# LCD.net
KiCad netlist of a schematic drawn in Altium Designer
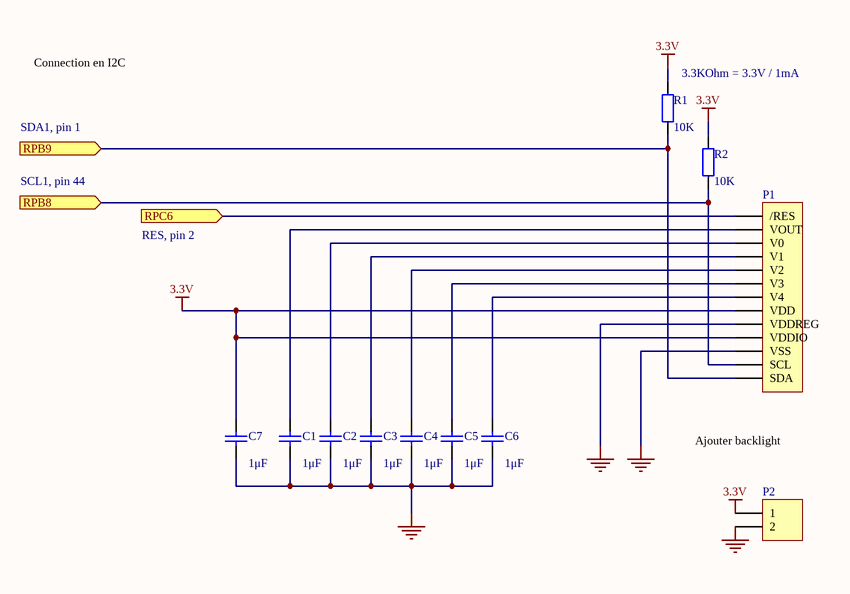
[diagram p0: LCD.SchDoc]

(export (version "E")
  (design (tool "Eeschema 10.0.6"))
  (components
    (comp (ref "C1")
      (value "1μF")
      (footprint "0603")
      (description "Capacitor")
      (fields (field (name "Comment") "Cap") (field (name "PUBLISHER") "Altium Limited"))
      (libsource (lib "Miscellaneous Devices") (part "Cap"))
    )
    (comp (ref "C2")
      (value "1μF")
      (footprint "0603")
      (description "Capacitor")
      (fields (field (name "Comment") "Cap") (field (name "PUBLISHER") "Altium Limited"))
      (libsource (lib "Miscellaneous Devices") (part "Cap"))
    )
    (comp (ref "C3")
      (value "1μF")
      (footprint "0603")
      (description "Capacitor")
      (fields (field (name "Comment") "Cap") (field (name "PUBLISHER") "Altium Limited"))
      (libsource (lib "Miscellaneous Devices") (part "Cap"))
    )
    (comp (ref "C4")
      (value "1μF")
      (footprint "0603")
      (description "Capacitor")
      (fields (field (name "Comment") "Cap") (field (name "PUBLISHER") "Altium Limited"))
      (libsource (lib "Miscellaneous Devices") (part "Cap"))
    )
    (comp (ref "C5")
      (value "1μF")
      (footprint "0603")
      (description "Capacitor")
      (fields (field (name "Comment") "Cap") (field (name "PUBLISHER") "Altium Limited"))
      (libsource (lib "Miscellaneous Devices") (part "Cap"))
    )
    (comp (ref "C6")
      (value "1μF")
      (footprint "0603")
      (description "Capacitor")
      (fields (field (name "Comment") "Cap") (field (name "PUBLISHER") "Altium Limited"))
      (libsource (lib "Miscellaneous Devices") (part "Cap"))
    )
    (comp (ref "C7")
      (value "1μF")
      (footprint "0603")
      (description "Capacitor")
      (fields (field (name "Comment") "Cap") (field (name "PUBLISHER") "Altium Limited"))
      (libsource (lib "Miscellaneous Devices") (part "Cap"))
    )
    (comp (ref "P1")
      (value "LCD")
      (footprint "lcd")
      (description "LCD Connector")
      (fields (field (name "PUBLISHER") "Altium Limited"))
      (libsource (lib "Miscellaneous Connectors") (part "Header 13"))
    )
    (comp (ref "P2")
      (value "lcd backlight")
      (footprint "lcd bk")
      (description "Header, 2-Pin, Right Angle")
      (libsource (lib "Miscellaneous Connectors") (part "Header 2H"))
    )
    (comp (ref "R1")
      (value "10K")
      (footprint "0603")
      (description "Resistor")
      (fields (field (name "Comment") "Res2") (field (name "PUBLISHER") "Altium Limited"))
      (libsource (lib "Miscellaneous Devices") (part "Res2"))
    )
    (comp (ref "R2")
      (value "10K")
      (footprint "0603")
      (description "Resistor")
      (fields (field (name "Comment") "Res2") (field (name "PUBLISHER") "Altium Limited"))
      (libsource (lib "Miscellaneous Devices") (part "Res2"))
    )
  )
  (nets
    (net (code "1") (name "/RPB8") (class "Default")
      (node (ref "P1") (pin "12") (pinfunction "SCL_12") (pintype "passive"))
      (node (ref "R2") (pin "1") (pinfunction "1_1") (pintype "passive"))
    )
    (net (code "2") (name "/RPB9") (class "Default")
      (node (ref "P1") (pin "13") (pinfunction "SDA_13") (pintype "passive"))
      (node (ref "R1") (pin "1") (pinfunction "1_1") (pintype "passive"))
    )
    (net (code "3") (name "/RPC6") (class "Default")
      (node (ref "P1") (pin "1") (pinfunction "/RES_1") (pintype "passive"))
    )
    (net (code "4") (name "3.3V") (class "Default")
      (node (ref "C7") (pin "2") (pinfunction "2_2") (pintype "passive"))
      (node (ref "P1") (pin "10") (pinfunction "VDDIO_10") (pintype "passive"))
      (node (ref "P1") (pin "8") (pinfunction "VDD_8") (pintype "passive"))
      (node (ref "P2") (pin "1") (pinfunction "1_1") (pintype "passive"))
      (node (ref "R1") (pin "2") (pinfunction "2_2") (pintype "passive"))
      (node (ref "R2") (pin "2") (pinfunction "2_2") (pintype "passive"))
    )
    (net (code "5") (name "GND") (class "Default")
      (node (ref "C1") (pin "1") (pinfunction "1_1") (pintype "passive"))
      (node (ref "C2") (pin "1") (pinfunction "1_1") (pintype "passive"))
      (node (ref "C3") (pin "1") (pinfunction "1_1") (pintype "passive"))
      (node (ref "C4") (pin "1") (pinfunction "1_1") (pintype "passive"))
      (node (ref "C5") (pin "1") (pinfunction "1_1") (pintype "passive"))
      (node (ref "C6") (pin "1") (pinfunction "1_1") (pintype "passive"))
      (node (ref "C7") (pin "1") (pinfunction "1_1") (pintype "passive"))
      (node (ref "P1") (pin "11") (pinfunction "VSS_11") (pintype "passive"))
      (node (ref "P1") (pin "9") (pinfunction "VDDREG_9") (pintype "passive"))
      (node (ref "P2") (pin "2") (pinfunction "2_2") (pintype "passive"))
    )
    (net (code "6") (name "Net-(P1-V0)") (class "Default")
      (node (ref "C2") (pin "2") (pinfunction "2_2") (pintype "passive"))
      (node (ref "P1") (pin "3") (pinfunction "V0_3") (pintype "passive"))
    )
    (net (code "7") (name "Net-(P1-V1)") (class "Default")
      (node (ref "C3") (pin "2") (pinfunction "2_2") (pintype "passive"))
      (node (ref "P1") (pin "4") (pinfunction "V1_4") (pintype "passive"))
    )
    (net (code "8") (name "Net-(P1-V2)") (class "Default")
      (node (ref "C4") (pin "2") (pinfunction "2_2") (pintype "passive"))
      (node (ref "P1") (pin "5") (pinfunction "V2_5") (pintype "passive"))
    )
    (net (code "9") (name "Net-(P1-V3)") (class "Default")
      (node (ref "C5") (pin "2") (pinfunction "2_2") (pintype "passive"))
      (node (ref "P1") (pin "6") (pinfunction "V3_6") (pintype "passive"))
    )
    (net (code "10") (name "Net-(P1-V4)") (class "Default")
      (node (ref "C6") (pin "2") (pinfunction "2_2") (pintype "passive"))
      (node (ref "P1") (pin "7") (pinfunction "V4_7") (pintype "passive"))
    )
    (net (code "11") (name "Net-(P1-VOUT)") (class "Default")
      (node (ref "C1") (pin "2") (pinfunction "2_2") (pintype "passive"))
      (node (ref "P1") (pin "2") (pinfunction "VOUT_2") (pintype "passive"))
    )
  )
)
